# GarageDoor.net
KiCad netlist of a schematic drawn in EAGLE
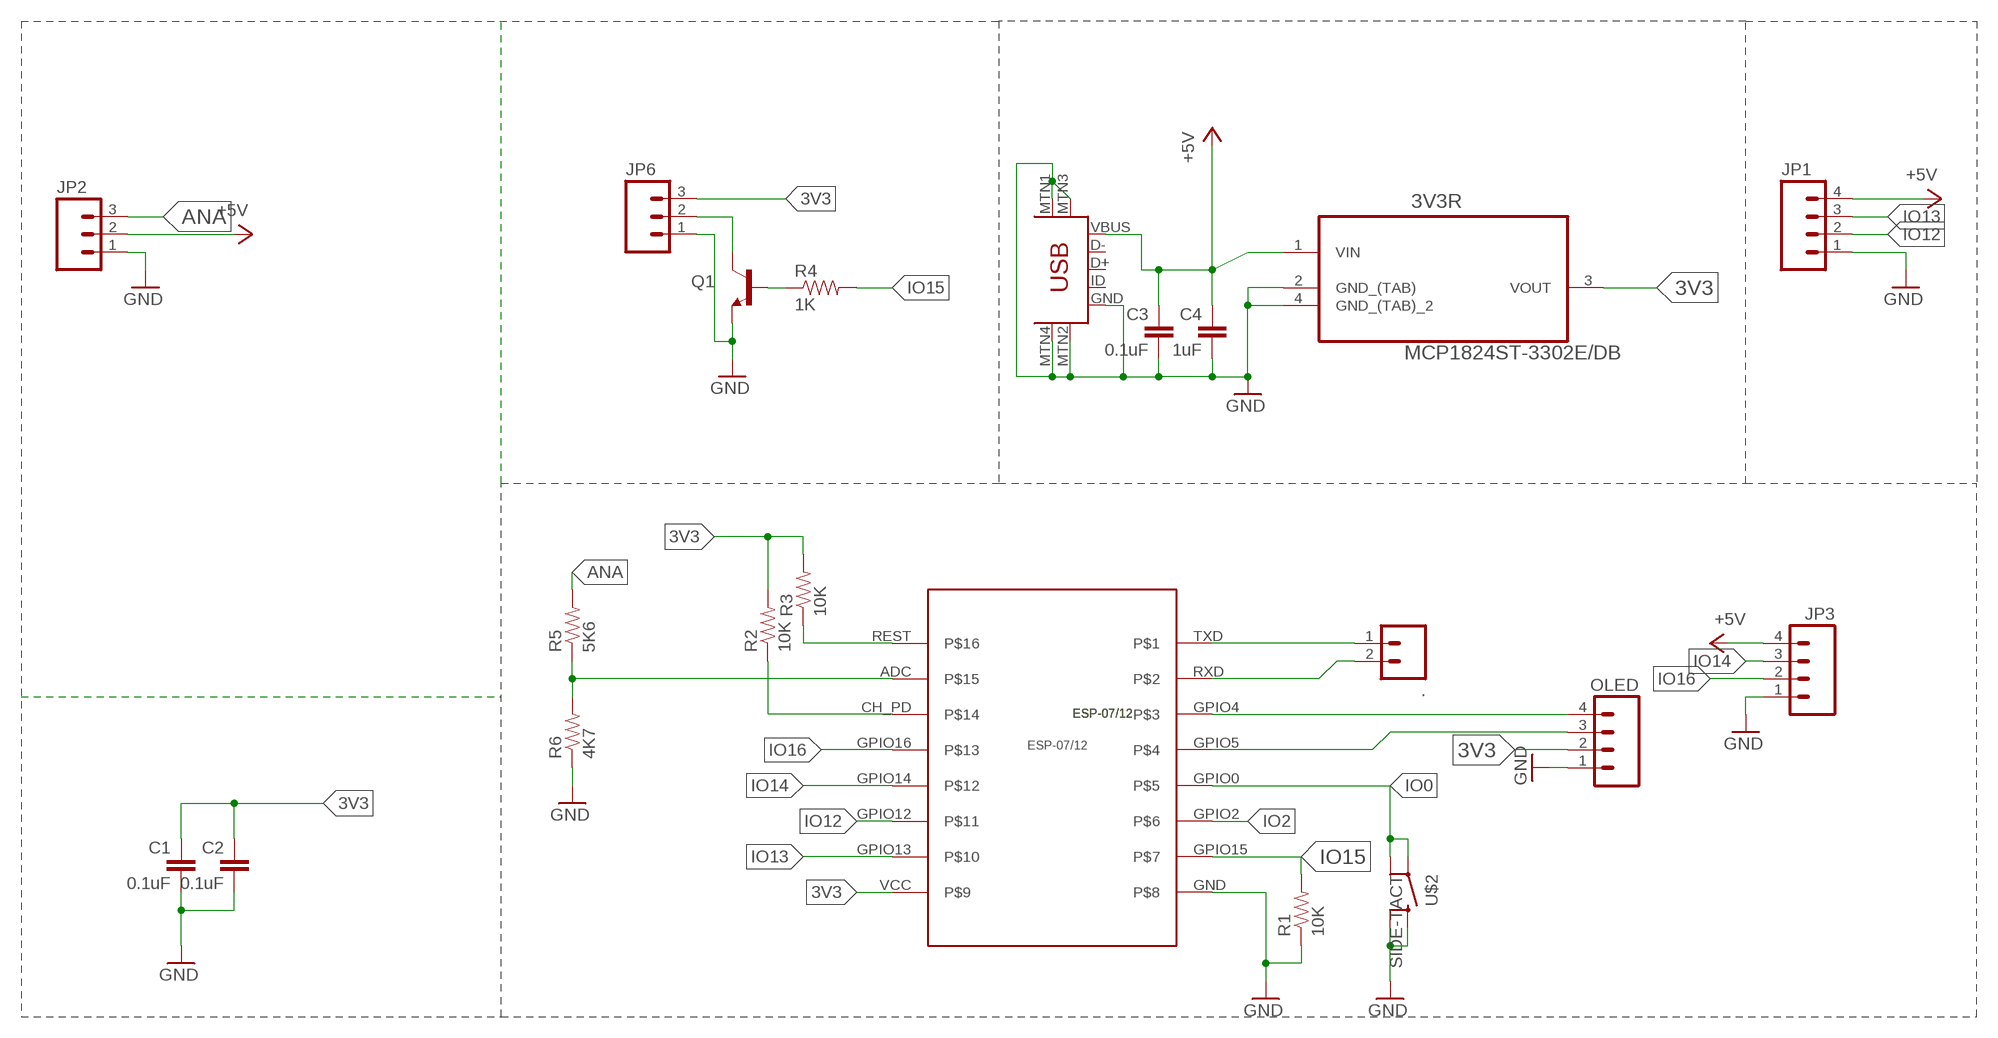
[diagram p0: schematic, sheet 1]

(export (version "E")
  (design (tool "Eeschema 10.0.6"))
  (components
    (comp (ref ".")
      (value "M02PTH")
      (footprint "eagle-import:1X02")
      (libsource (lib "eagle-import") (part "M02PTH"))
    )
    (comp (ref "3V3R")
      (value "MCP1824ST-3302E/DB")
      (footprint "eagle-import:SOT230P700X180-4N")
      (libsource (lib "eagle-import") (part "MCP1824ST-3302E/DB"))
    )
    (comp (ref "C1")
      (value "0.1uF")
      (footprint "eagle-import:0805-CAP")
      (libsource (lib "eagle-import") (part "CAP"))
    )
    (comp (ref "C2")
      (value "0.1uF")
      (footprint "eagle-import:0805-CAP")
      (libsource (lib "eagle-import") (part "CAP"))
    )
    (comp (ref "C3")
      (value "0.1uF")
      (footprint "eagle-import:0805-CAP")
      (libsource (lib "eagle-import") (part "CAP"))
    )
    (comp (ref "C4")
      (value "1uF")
      (footprint "eagle-import:0805-CAP")
      (libsource (lib "eagle-import") (part "CAP"))
    )
    (comp (ref "JP1")
      (value "M04POLAR")
      (footprint "eagle-import:MOLEX-1X4")
      (libsource (lib "eagle-import") (part "M04POLAR"))
    )
    (comp (ref "JP2")
      (value "M03POLAR")
      (footprint "eagle-import:MOLEX-1X3")
      (libsource (lib "eagle-import") (part "M03POLAR"))
    )
    (comp (ref "JP3")
      (value "M04POLAR")
      (footprint "eagle-import:MOLEX-1X4")
      (libsource (lib "eagle-import") (part "M04POLAR"))
    )
    (comp (ref "JP6")
      (value "M03POLAR")
      (footprint "eagle-import:MOLEX-1X3")
      (libsource (lib "eagle-import") (part "M03POLAR"))
    )
    (comp (ref "OLED")
      (value "M04PTH")
      (footprint "eagle-import:1X04")
      (libsource (lib "eagle-import") (part "M04PTH"))
    )
    (comp (ref "Q1")
      (value "TRANSISTOR_NPNSOT23-3")
      (footprint "eagle-import:SOT23-3")
      (libsource (lib "eagle-import") (part "TRANSISTOR_NPNSOT23-3"))
    )
    (comp (ref "R1")
      (value "10K")
      (footprint "eagle-import:0805")
      (libsource (lib "eagle-import") (part "RESISTOR0805-RES"))
    )
    (comp (ref "R2")
      (value "10K")
      (footprint "eagle-import:0805")
      (libsource (lib "eagle-import") (part "RESISTOR0805-RES"))
    )
    (comp (ref "R3")
      (value "10K")
      (footprint "eagle-import:0805")
      (libsource (lib "eagle-import") (part "RESISTOR0805-RES"))
    )
    (comp (ref "R4")
      (value "1K")
      (footprint "eagle-import:0805")
      (libsource (lib "eagle-import") (part "RESISTOR0805-RES"))
    )
    (comp (ref "R5")
      (value "5K6")
      (footprint "eagle-import:0805")
      (libsource (lib "eagle-import") (part "RESISTOR0805-RES"))
    )
    (comp (ref "R6")
      (value "4K7")
      (footprint "eagle-import:0805")
      (libsource (lib "eagle-import") (part "RESISTOR0805-RES"))
    )
    (comp (ref "U$1")
      (value "ESP-07/12")
      (footprint "eagle-import:ESP-07_12")
      (libsource (lib "eagle-import") (part "ESP-07/12"))
    )
    (comp (ref "U$2")
      (value "SIDE-TACT")
      (footprint "eagle-import:SIDE-TACT")
      (libsource (lib "eagle-import") (part "SIDE-TACT"))
    )
    (comp (ref "U$4")
      (value "USB-MINIB-5PIN")
      (footprint "eagle-import:USB-MINIB")
      (libsource (lib "eagle-import") (part "USB-MINIB-5PIN"))
    )
  )
  (nets
    (net (code "1") (name "+5V") (class "Default")
      (node (ref "3V3R") (pin "1") (pinfunction "VIN_1") (pintype "input"))
      (node (ref "C3") (pin "1") (pinfunction "1_1") (pintype "passive"))
      (node (ref "C4") (pin "1") (pinfunction "1_1") (pintype "passive"))
      (node (ref "JP1") (pin "4") (pinfunction "4_4") (pintype "passive"))
      (node (ref "JP2") (pin "2") (pinfunction "2_2") (pintype "passive"))
      (node (ref "JP3") (pin "4") (pinfunction "4_4") (pintype "passive"))
      (node (ref "U$4") (pin "VBUS") (pinfunction "VBUS_VBUS") (pintype "bidirectional"))
    )
    (net (code "2") (name "3V3") (class "Default")
      (node (ref "3V3R") (pin "3") (pinfunction "VOUT_3") (pintype "output"))
      (node (ref "C1") (pin "1") (pinfunction "1_1") (pintype "passive"))
      (node (ref "C2") (pin "1") (pinfunction "1_1") (pintype "passive"))
      (node (ref "JP6") (pin "3") (pinfunction "3_3") (pintype "passive"))
      (node (ref "OLED") (pin "2") (pinfunction "2_2") (pintype "passive"))
      (node (ref "R2") (pin "2") (pinfunction "2_2") (pintype "passive"))
      (node (ref "R3") (pin "2") (pinfunction "2_2") (pintype "passive"))
      (node (ref "U$1") (pin "VCC") (pinfunction "P$9_VCC") (pintype "bidirectional"))
    )
    (net (code "3") (name "ANA") (class "Default")
      (node (ref "JP2") (pin "3") (pinfunction "3_3") (pintype "passive"))
      (node (ref "R5") (pin "2") (pinfunction "2_2") (pintype "passive"))
    )
    (net (code "4") (name "GND") (class "Default")
      (node (ref "3V3R") (pin "2") (pinfunction "GND_(TAB)_2") (pintype "passive"))
      (node (ref "3V3R") (pin "4") (pinfunction "GND_(TAB)_2_4") (pintype "passive"))
      (node (ref "C1") (pin "2") (pinfunction "2_2") (pintype "passive"))
      (node (ref "C2") (pin "2") (pinfunction "2_2") (pintype "passive"))
      (node (ref "C3") (pin "2") (pinfunction "2_2") (pintype "passive"))
      (node (ref "C4") (pin "2") (pinfunction "2_2") (pintype "passive"))
      (node (ref "JP1") (pin "1") (pinfunction "1_1") (pintype "passive"))
      (node (ref "JP2") (pin "1") (pinfunction "1_1") (pintype "passive"))
      (node (ref "JP3") (pin "1") (pinfunction "1_1") (pintype "passive"))
      (node (ref "JP6") (pin "1") (pinfunction "1_1") (pintype "passive"))
      (node (ref "OLED") (pin "1") (pinfunction "1_1") (pintype "passive"))
      (node (ref "Q1") (pin "2") (pinfunction "E_2") (pintype "passive"))
      (node (ref "R1") (pin "1") (pinfunction "1_1") (pintype "passive"))
      (node (ref "R6") (pin "1") (pinfunction "1_1") (pintype "passive"))
      (node (ref "U$1") (pin "GND") (pinfunction "P$8_GND") (pintype "bidirectional"))
      (node (ref "U$2") (pin "3") (pinfunction "2_3") (pintype "passive"))
      (node (ref "U$2") (pin "4") (pinfunction "4_4") (pintype "passive"))
      (node (ref "U$4") (pin "GND") (pinfunction "GND_GND") (pintype "bidirectional"))
      (node (ref "U$4") (pin "MTN1") (pinfunction "MTN2_MTN1") (pintype "bidirectional"))
      (node (ref "U$4") (pin "MTN2") (pinfunction "MTN3_MTN2") (pintype "bidirectional"))
      (node (ref "U$4") (pin "MTN3") (pinfunction "MTN1_MTN3") (pintype "bidirectional"))
      (node (ref "U$4") (pin "MTN4") (pinfunction "MTN4_MTN4") (pintype "bidirectional"))
    )
    (net (code "5") (name "IO0") (class "Default")
      (node (ref "U$1") (pin "GPIO0") (pinfunction "P$5_GPIO0") (pintype "bidirectional"))
      (node (ref "U$2") (pin "1") (pinfunction "1_1") (pintype "passive"))
      (node (ref "U$2") (pin "2") (pinfunction "3_2") (pintype "passive"))
    )
    (net (code "6") (name "IO2") (class "Default")
      (node (ref "U$1") (pin "GPIO2") (pinfunction "P$6_GPIO2") (pintype "bidirectional"))
    )
    (net (code "7") (name "IO12") (class "Default")
      (node (ref "JP1") (pin "2") (pinfunction "2_2") (pintype "passive"))
      (node (ref "U$1") (pin "GPIO12") (pinfunction "P$11_GPIO12") (pintype "bidirectional"))
    )
    (net (code "8") (name "IO13") (class "Default")
      (node (ref "JP1") (pin "3") (pinfunction "3_3") (pintype "passive"))
      (node (ref "U$1") (pin "GPIO13") (pinfunction "P$10_GPIO13") (pintype "bidirectional"))
    )
    (net (code "9") (name "IO14") (class "Default")
      (node (ref "JP3") (pin "3") (pinfunction "3_3") (pintype "passive"))
      (node (ref "U$1") (pin "GPIO14") (pinfunction "P$12_GPIO14") (pintype "bidirectional"))
    )
    (net (code "10") (name "IO15") (class "Default")
      (node (ref "R1") (pin "2") (pinfunction "2_2") (pintype "passive"))
      (node (ref "R4") (pin "2") (pinfunction "2_2") (pintype "passive"))
      (node (ref "U$1") (pin "GPIO15") (pinfunction "P$7_GPIO15") (pintype "bidirectional"))
    )
    (net (code "11") (name "IO16") (class "Default")
      (node (ref "JP3") (pin "2") (pinfunction "2_2") (pintype "passive"))
      (node (ref "U$1") (pin "GPIO16") (pinfunction "P$13_GPIO16") (pintype "bidirectional"))
    )
    (net (code "12") (name "Net-(Q1-B)") (class "Default")
      (node (ref "Q1") (pin "1") (pinfunction "B_1") (pintype "passive"))
      (node (ref "R4") (pin "1") (pinfunction "1_1") (pintype "passive"))
    )
    (net (code "13") (name "Net-(Q1-C)") (class "Default")
      (node (ref "JP6") (pin "2") (pinfunction "2_2") (pintype "passive"))
      (node (ref "Q1") (pin "3") (pinfunction "C_3") (pintype "passive"))
    )
    (net (code "14") (name "Net-(U$1-P$1)") (class "Default")
      (node (ref ".") (pin "1") (pinfunction "1_1") (pintype "passive"))
      (node (ref "U$1") (pin "TXD") (pinfunction "P$1_TXD") (pintype "bidirectional"))
    )
    (net (code "15") (name "Net-(U$1-P$2)") (class "Default")
      (node (ref ".") (pin "2") (pinfunction "2_2") (pintype "passive"))
      (node (ref "U$1") (pin "RXD") (pinfunction "P$2_RXD") (pintype "bidirectional"))
    )
    (net (code "16") (name "Net-(U$1-P$3)") (class "Default")
      (node (ref "OLED") (pin "4") (pinfunction "4_4") (pintype "passive"))
      (node (ref "U$1") (pin "GPIO4") (pinfunction "P$3_GPIO4") (pintype "bidirectional"))
    )
    (net (code "17") (name "Net-(U$1-P$4)") (class "Default")
      (node (ref "OLED") (pin "3") (pinfunction "3_3") (pintype "passive"))
      (node (ref "U$1") (pin "GPIO5") (pinfunction "P$4_GPIO5") (pintype "bidirectional"))
    )
    (net (code "18") (name "Net-(U$1-P$14)") (class "Default")
      (node (ref "R2") (pin "1") (pinfunction "1_1") (pintype "passive"))
      (node (ref "U$1") (pin "CH_PD") (pinfunction "P$14_CH_PD") (pintype "bidirectional"))
    )
    (net (code "19") (name "Net-(U$1-P$15)") (class "Default")
      (node (ref "R5") (pin "1") (pinfunction "1_1") (pintype "passive"))
      (node (ref "R6") (pin "2") (pinfunction "2_2") (pintype "passive"))
      (node (ref "U$1") (pin "ADC") (pinfunction "P$15_ADC") (pintype "bidirectional"))
    )
    (net (code "20") (name "Net-(U$1-P$16)") (class "Default")
      (node (ref "R3") (pin "1") (pinfunction "1_1") (pintype "passive"))
      (node (ref "U$1") (pin "REST") (pinfunction "P$16_REST") (pintype "bidirectional"))
    )
    (net (code "21") (name "unconnected-(U$4-PadD+)") (class "Default")
      (node (ref "U$4") (pin "D+") (pinfunction "D+_D+") (pintype "bidirectional"))
    )
    (net (code "22") (name "unconnected-(U$4-PadD-)") (class "Default")
      (node (ref "U$4") (pin "D-") (pinfunction "D-_D-") (pintype "bidirectional"))
    )
    (net (code "23") (name "unconnected-(U$4-PadID)") (class "Default")
      (node (ref "U$4") (pin "ID") (pinfunction "ID_ID") (pintype "bidirectional"))
    )
  )
)
